# FenixCasePowerBoard.net
KiCad netlist of a schematic drawn in EAGLE
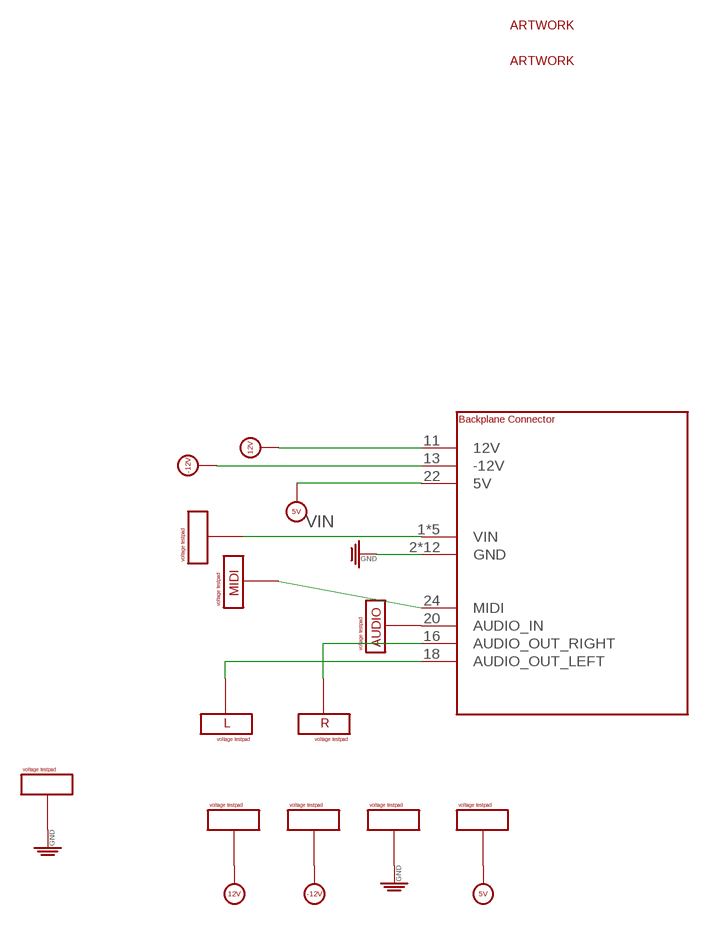
[diagram p0: schematic, sheet 1]
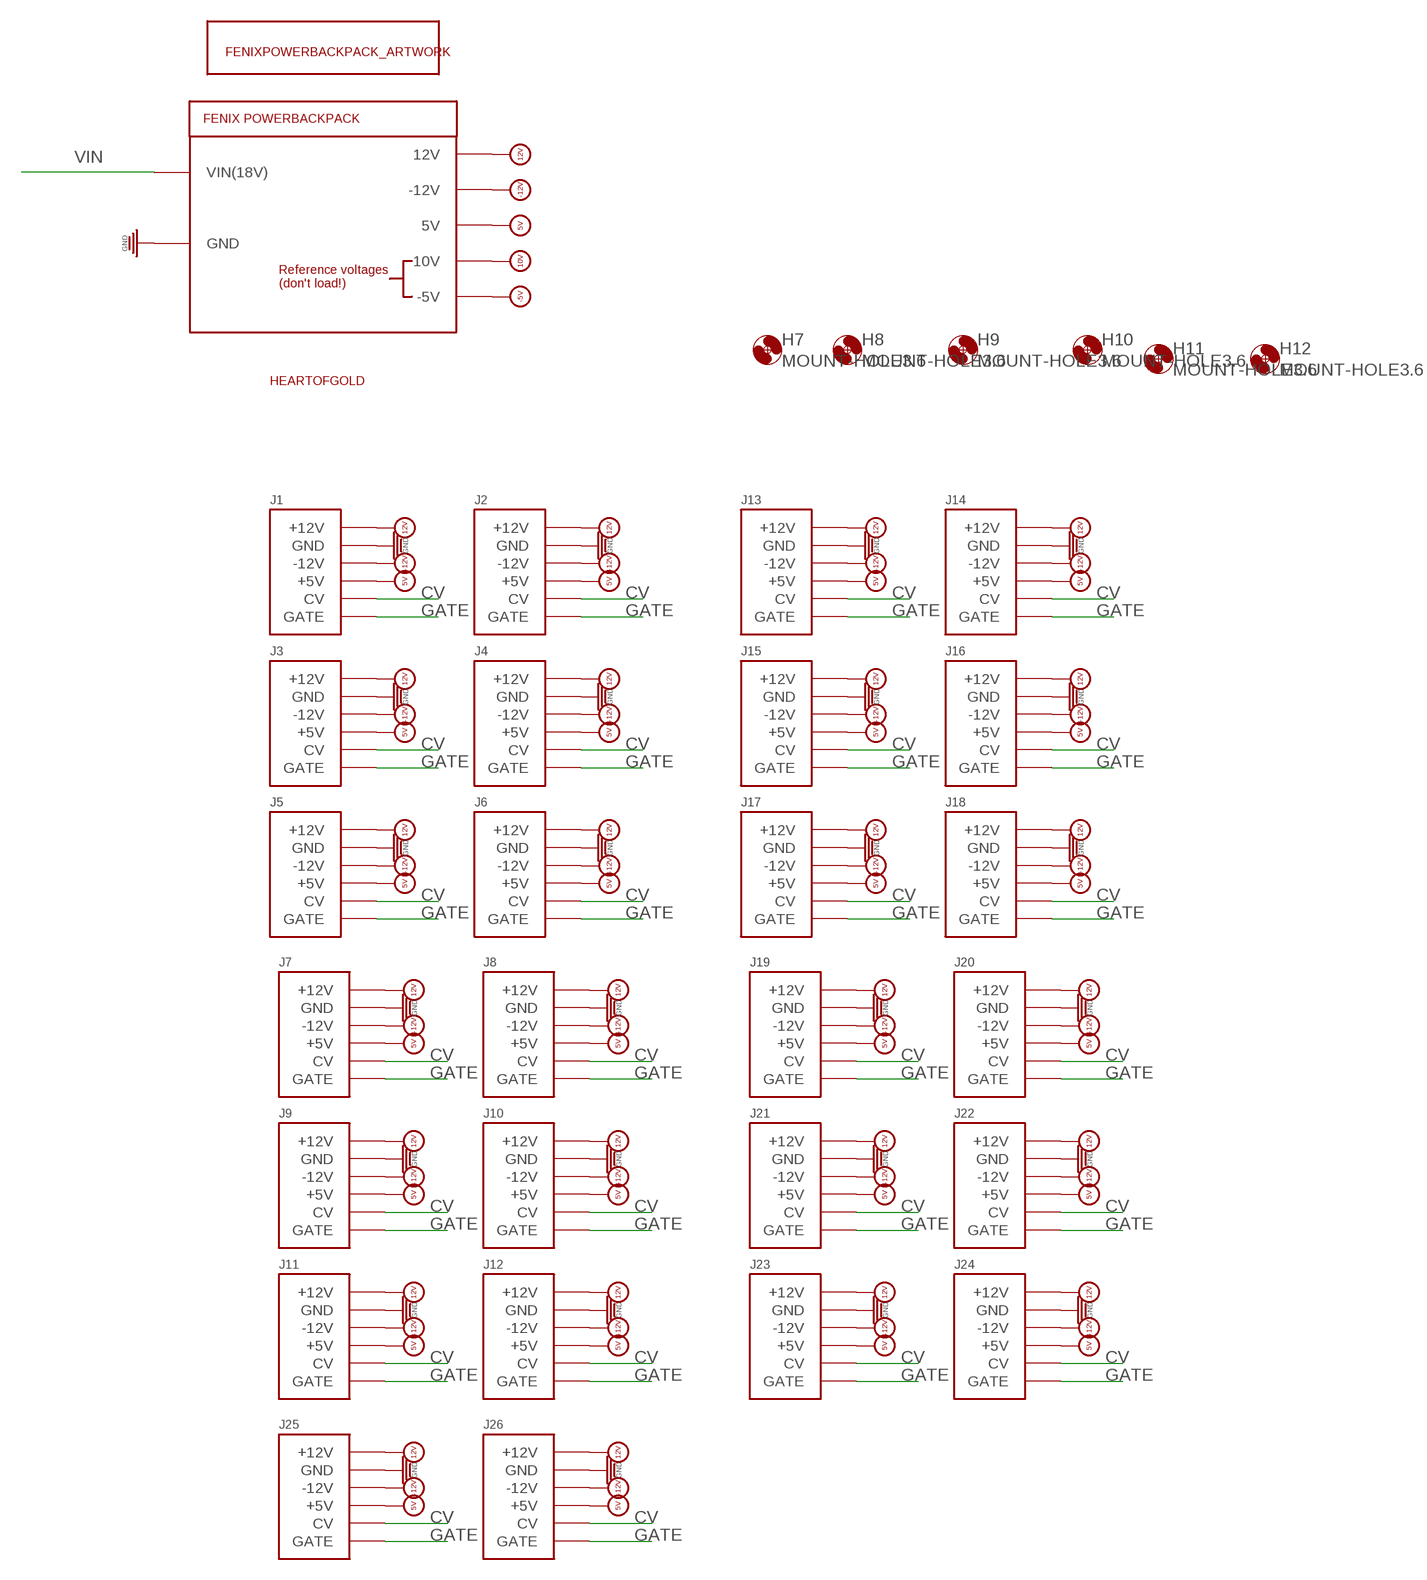
[diagram p1: schematic, sheet 3]

(export (version "E")
  (design (tool "Eeschema 10.0.6"))
  (components
    (comp (ref "H7")
      (value "MOUNT-HOLE3.6")
      (footprint "eagle-import:3,6")
      (libsource (lib "eagle-import") (part "MOUNT-HOLE3.6"))
    )
    (comp (ref "H8")
      (value "MOUNT-HOLE3.6")
      (footprint "eagle-import:3,6")
      (libsource (lib "eagle-import") (part "MOUNT-HOLE3.6"))
    )
    (comp (ref "H9")
      (value "MOUNT-HOLE3.6")
      (footprint "eagle-import:3,6")
      (libsource (lib "eagle-import") (part "MOUNT-HOLE3.6"))
    )
    (comp (ref "H10")
      (value "MOUNT-HOLE3.6")
      (footprint "eagle-import:3,6")
      (libsource (lib "eagle-import") (part "MOUNT-HOLE3.6"))
    )
    (comp (ref "H11")
      (value "MOUNT-HOLE3.6")
      (footprint "eagle-import:3,6")
      (libsource (lib "eagle-import") (part "MOUNT-HOLE3.6"))
    )
    (comp (ref "H12")
      (value "MOUNT-HOLE3.6")
      (footprint "eagle-import:3,6")
      (libsource (lib "eagle-import") (part "MOUNT-HOLE3.6"))
    )
    (comp (ref "J1")
      (value "POWERSHROUDED")
      (footprint "eagle-import:POWER_16_SHROUDED")
      (libsource (lib "eagle-import") (part "POWERSHROUDED"))
    )
    (comp (ref "J2")
      (value "POWERSHROUDED")
      (footprint "eagle-import:POWER_16_SHROUDED")
      (libsource (lib "eagle-import") (part "POWERSHROUDED"))
    )
    (comp (ref "J3")
      (value "POWERSHROUDED")
      (footprint "eagle-import:POWER_16_SHROUDED")
      (libsource (lib "eagle-import") (part "POWERSHROUDED"))
    )
    (comp (ref "J4")
      (value "POWERSHROUDED")
      (footprint "eagle-import:POWER_16_SHROUDED")
      (libsource (lib "eagle-import") (part "POWERSHROUDED"))
    )
    (comp (ref "J5")
      (value "POWERSHROUDED")
      (footprint "eagle-import:POWER_16_SHROUDED")
      (libsource (lib "eagle-import") (part "POWERSHROUDED"))
    )
    (comp (ref "J6")
      (value "POWERSHROUDED")
      (footprint "eagle-import:POWER_16_SHROUDED")
      (libsource (lib "eagle-import") (part "POWERSHROUDED"))
    )
    (comp (ref "J7")
      (value "POWERSHROUDED")
      (footprint "eagle-import:POWER_16_SHROUDED")
      (libsource (lib "eagle-import") (part "POWERSHROUDED"))
    )
    (comp (ref "J8")
      (value "POWERSHROUDED")
      (footprint "eagle-import:POWER_16_SHROUDED")
      (libsource (lib "eagle-import") (part "POWERSHROUDED"))
    )
    (comp (ref "J9")
      (value "POWERSHROUDED")
      (footprint "eagle-import:POWER_16_SHROUDED")
      (libsource (lib "eagle-import") (part "POWERSHROUDED"))
    )
    (comp (ref "J10")
      (value "POWERSHROUDED")
      (footprint "eagle-import:POWER_16_SHROUDED")
      (libsource (lib "eagle-import") (part "POWERSHROUDED"))
    )
    (comp (ref "J11")
      (value "POWERSHROUDED")
      (footprint "eagle-import:POWER_16_SHROUDED")
      (libsource (lib "eagle-import") (part "POWERSHROUDED"))
    )
    (comp (ref "J12")
      (value "POWERSHROUDED")
      (footprint "eagle-import:POWER_16_SHROUDED")
      (libsource (lib "eagle-import") (part "POWERSHROUDED"))
    )
    (comp (ref "J13")
      (value "POWERSHROUDED")
      (footprint "eagle-import:POWER_16_SHROUDED")
      (libsource (lib "eagle-import") (part "POWERSHROUDED"))
    )
    (comp (ref "J14")
      (value "POWERSHROUDED")
      (footprint "eagle-import:POWER_16_SHROUDED")
      (libsource (lib "eagle-import") (part "POWERSHROUDED"))
    )
    (comp (ref "J15")
      (value "POWERSHROUDED")
      (footprint "eagle-import:POWER_16_SHROUDED")
      (libsource (lib "eagle-import") (part "POWERSHROUDED"))
    )
    (comp (ref "J16")
      (value "POWERSHROUDED")
      (footprint "eagle-import:POWER_16_SHROUDED")
      (libsource (lib "eagle-import") (part "POWERSHROUDED"))
    )
    (comp (ref "J17")
      (value "POWERSHROUDED")
      (footprint "eagle-import:POWER_16_SHROUDED")
      (libsource (lib "eagle-import") (part "POWERSHROUDED"))
    )
    (comp (ref "J18")
      (value "POWERSHROUDED")
      (footprint "eagle-import:POWER_16_SHROUDED")
      (libsource (lib "eagle-import") (part "POWERSHROUDED"))
    )
    (comp (ref "J19")
      (value "POWERSHROUDED")
      (footprint "eagle-import:POWER_16_SHROUDED")
      (libsource (lib "eagle-import") (part "POWERSHROUDED"))
    )
    (comp (ref "J20")
      (value "POWERSHROUDED")
      (footprint "eagle-import:POWER_16_SHROUDED")
      (libsource (lib "eagle-import") (part "POWERSHROUDED"))
    )
    (comp (ref "J21")
      (value "POWERSHROUDED")
      (footprint "eagle-import:POWER_16_SHROUDED")
      (libsource (lib "eagle-import") (part "POWERSHROUDED"))
    )
    (comp (ref "J22")
      (value "POWERSHROUDED")
      (footprint "eagle-import:POWER_16_SHROUDED")
      (libsource (lib "eagle-import") (part "POWERSHROUDED"))
    )
    (comp (ref "J23")
      (value "POWERSHROUDED")
      (footprint "eagle-import:POWER_16_SHROUDED")
      (libsource (lib "eagle-import") (part "POWERSHROUDED"))
    )
    (comp (ref "J24")
      (value "POWERSHROUDED")
      (footprint "eagle-import:POWER_16_SHROUDED")
      (libsource (lib "eagle-import") (part "POWERSHROUDED"))
    )
    (comp (ref "J25")
      (value "POWERSHROUDED")
      (footprint "eagle-import:POWER_16_SHROUDED")
      (libsource (lib "eagle-import") (part "POWERSHROUDED"))
    )
    (comp (ref "J26")
      (value "POWERSHROUDED")
      (footprint "eagle-import:POWER_16_SHROUDED")
      (libsource (lib "eagle-import") (part "POWERSHROUDED"))
    )
    (comp (ref "U$5")
      (value "FENIXPOWERBACKPACKART_MODULE")
      (footprint "eagle-import:FENIXPOWERBACKPACK_MODULE")
      (libsource (lib "eagle-import") (part "FENIXPOWERBACKPACKART_MODULE"))
    )
    (comp (ref "U$10")
      (value "HEARTOFGOLD")
      (footprint "eagle-import:HEARTOFGOLD")
      (libsource (lib "eagle-import") (part "HEARTOFGOLD"))
    )
    (comp (ref "U$31")
      (value "FENIXPOWERBACKPACK_MODULE")
      (footprint "eagle-import:FENIXPOWERBACKPACK")
      (libsource (lib "eagle-import") (part "FENIXPOWERBACKPACK_MODULE"))
    )
    (comp (ref "U$1")
      (value "VOLTAGETESTPAD")
      (footprint "eagle-import:POWERTESTPAD")
      (fields (field (name "DESC") "MIDI"))
      (libsource (lib "eagle-import") (part "VOLTAGETESTPAD"))
    )
    (comp (ref "U$2")
      (value "VOLTAGETESTPAD")
      (footprint "eagle-import:POWERTESTPAD")
      (fields (field (name "DESC") "AUDIO"))
      (libsource (lib "eagle-import") (part "VOLTAGETESTPAD"))
    )
    (comp (ref "U$4")
      (value "VOLTAGETESTPAD_BIG")
      (footprint "eagle-import:POWERTESTPAD_BIG")
      (fields (field (name "DESC") "-12V"))
      (libsource (lib "eagle-import") (part "VOLTAGETESTPAD_BIG"))
    )
    (comp (ref "U$6")
      (value "VOLTAGETESTPAD_BIG")
      (footprint "eagle-import:POWERTESTPAD_BIG")
      (fields (field (name "DESC") "GND"))
      (libsource (lib "eagle-import") (part "VOLTAGETESTPAD_BIG"))
    )
    (comp (ref "U$7")
      (value "VOLTAGETESTPAD_BIG")
      (footprint "eagle-import:POWERTESTPAD_BIG")
      (fields (field (name "DESC") "5V"))
      (libsource (lib "eagle-import") (part "VOLTAGETESTPAD_BIG"))
    )
    (comp (ref "U$8")
      (value "BACKPLANECONNECTOR_VINPLANE")
      (footprint "eagle-import:BACKPLANECONNECTOR")
      (fields (field (name "DESC") "PowerSupplyInput"))
      (libsource (lib "eagle-import") (part "BACKPLANECONNECTOR_VINPLANE"))
    )
    (comp (ref "U$12")
      (value "VOLTAGETESTPAD_BIG")
      (footprint "eagle-import:POWERTESTPAD_BIG")
      (fields (field (name "DESC") "12V"))
      (libsource (lib "eagle-import") (part "VOLTAGETESTPAD_BIG"))
    )
    (comp (ref "U$20")
      (value "TINRS_ARTWORKTINYDATE")
      (footprint "eagle-import:JUSTATINYROCKET_DATECODE")
      (libsource (lib "eagle-import") (part "TINRS_ARTWORKTINYDATE"))
    )
    (comp (ref "U$21")
      (value "TINRS_ARTWORKTINYDATE")
      (footprint "eagle-import:JUSTATINYROCKET_DATECODE")
      (libsource (lib "eagle-import") (part "TINRS_ARTWORKTINYDATE"))
    )
    (comp (ref "U$29")
      (value "VOLTAGETESTPAD")
      (footprint "eagle-import:POWERTESTPAD")
      (fields (field (name "DESC") "L"))
      (libsource (lib "eagle-import") (part "VOLTAGETESTPAD"))
    )
    (comp (ref "U$30")
      (value "VOLTAGETESTPAD")
      (footprint "eagle-import:POWERTESTPAD")
      (fields (field (name "DESC") "R"))
      (libsource (lib "eagle-import") (part "VOLTAGETESTPAD"))
    )
    (comp (ref "U$104")
      (value "VOLTAGETESTPAD_BIG")
      (footprint "eagle-import:POWERTESTPAD_BIG")
      (fields (field (name "DESC") "VIN"))
      (libsource (lib "eagle-import") (part "VOLTAGETESTPAD_BIG"))
    )
    (comp (ref "U$105")
      (value "VOLTAGETESTPAD_BIG")
      (footprint "eagle-import:POWERTESTPAD_BIG")
      (fields (field (name "DESC") "GND"))
      (libsource (lib "eagle-import") (part "VOLTAGETESTPAD_BIG"))
    )
  )
  (nets
    (net (code "1") (name "-5V") (class "Default")
      (node (ref "U$31") (pin "-5V") (pinfunction "-5V_-5V") (pintype "bidirectional"))
      (node (ref "U$31") (pin "-5V@2") (pinfunction "-5V_-5V@2") (pintype "bidirectional"))
    )
    (net (code "2") (name "-12V") (class "Default")
      (node (ref "J1") (pin "1") (pinfunction "-12V_1") (pintype "bidirectional"))
      (node (ref "J1") (pin "2") (pinfunction "-12V_2") (pintype "bidirectional"))
      (node (ref "J10") (pin "1") (pinfunction "-12V_1") (pintype "bidirectional"))
      (node (ref "J10") (pin "2") (pinfunction "-12V_2") (pintype "bidirectional"))
      (node (ref "J11") (pin "1") (pinfunction "-12V_1") (pintype "bidirectional"))
      (node (ref "J11") (pin "2") (pinfunction "-12V_2") (pintype "bidirectional"))
      (node (ref "J12") (pin "1") (pinfunction "-12V_1") (pintype "bidirectional"))
      (node (ref "J12") (pin "2") (pinfunction "-12V_2") (pintype "bidirectional"))
      (node (ref "J13") (pin "1") (pinfunction "-12V_1") (pintype "bidirectional"))
      (node (ref "J13") (pin "2") (pinfunction "-12V_2") (pintype "bidirectional"))
      (node (ref "J14") (pin "1") (pinfunction "-12V_1") (pintype "bidirectional"))
      (node (ref "J14") (pin "2") (pinfunction "-12V_2") (pintype "bidirectional"))
      (node (ref "J15") (pin "1") (pinfunction "-12V_1") (pintype "bidirectional"))
      (node (ref "J15") (pin "2") (pinfunction "-12V_2") (pintype "bidirectional"))
      (node (ref "J16") (pin "1") (pinfunction "-12V_1") (pintype "bidirectional"))
      (node (ref "J16") (pin "2") (pinfunction "-12V_2") (pintype "bidirectional"))
      (node (ref "J17") (pin "1") (pinfunction "-12V_1") (pintype "bidirectional"))
      (node (ref "J17") (pin "2") (pinfunction "-12V_2") (pintype "bidirectional"))
      (node (ref "J18") (pin "1") (pinfunction "-12V_1") (pintype "bidirectional"))
      (node (ref "J18") (pin "2") (pinfunction "-12V_2") (pintype "bidirectional"))
      (node (ref "J19") (pin "1") (pinfunction "-12V_1") (pintype "bidirectional"))
      (node (ref "J19") (pin "2") (pinfunction "-12V_2") (pintype "bidirectional"))
      (node (ref "J2") (pin "1") (pinfunction "-12V_1") (pintype "bidirectional"))
      (node (ref "J2") (pin "2") (pinfunction "-12V_2") (pintype "bidirectional"))
      (node (ref "J20") (pin "1") (pinfunction "-12V_1") (pintype "bidirectional"))
      (node (ref "J20") (pin "2") (pinfunction "-12V_2") (pintype "bidirectional"))
      (node (ref "J21") (pin "1") (pinfunction "-12V_1") (pintype "bidirectional"))
      (node (ref "J21") (pin "2") (pinfunction "-12V_2") (pintype "bidirectional"))
      (node (ref "J22") (pin "1") (pinfunction "-12V_1") (pintype "bidirectional"))
      (node (ref "J22") (pin "2") (pinfunction "-12V_2") (pintype "bidirectional"))
      (node (ref "J23") (pin "1") (pinfunction "-12V_1") (pintype "bidirectional"))
      (node (ref "J23") (pin "2") (pinfunction "-12V_2") (pintype "bidirectional"))
      (node (ref "J24") (pin "1") (pinfunction "-12V_1") (pintype "bidirectional"))
      (node (ref "J24") (pin "2") (pinfunction "-12V_2") (pintype "bidirectional"))
      (node (ref "J25") (pin "1") (pinfunction "-12V_1") (pintype "bidirectional"))
      (node (ref "J25") (pin "2") (pinfunction "-12V_2") (pintype "bidirectional"))
      (node (ref "J26") (pin "1") (pinfunction "-12V_1") (pintype "bidirectional"))
      (node (ref "J26") (pin "2") (pinfunction "-12V_2") (pintype "bidirectional"))
      (node (ref "J3") (pin "1") (pinfunction "-12V_1") (pintype "bidirectional"))
      (node (ref "J3") (pin "2") (pinfunction "-12V_2") (pintype "bidirectional"))
      (node (ref "J4") (pin "1") (pinfunction "-12V_1") (pintype "bidirectional"))
      (node (ref "J4") (pin "2") (pinfunction "-12V_2") (pintype "bidirectional"))
      (node (ref "J5") (pin "1") (pinfunction "-12V_1") (pintype "bidirectional"))
      (node (ref "J5") (pin "2") (pinfunction "-12V_2") (pintype "bidirectional"))
      (node (ref "J6") (pin "1") (pinfunction "-12V_1") (pintype "bidirectional"))
      (node (ref "J6") (pin "2") (pinfunction "-12V_2") (pintype "bidirectional"))
      (node (ref "J7") (pin "1") (pinfunction "-12V_1") (pintype "bidirectional"))
      (node (ref "J7") (pin "2") (pinfunction "-12V_2") (pintype "bidirectional"))
      (node (ref "J8") (pin "1") (pinfunction "-12V_1") (pintype "bidirectional"))
      (node (ref "J8") (pin "2") (pinfunction "-12V_2") (pintype "bidirectional"))
      (node (ref "J9") (pin "1") (pinfunction "-12V_1") (pintype "bidirectional"))
      (node (ref "J9") (pin "2") (pinfunction "-12V_2") (pintype "bidirectional"))
      (node (ref "U$31") (pin "-12V@1") (pinfunction "-12V_-12V@1") (pintype "bidirectional"))
      (node (ref "U$31") (pin "-12V@2") (pinfunction "-12V_-12V@2") (pintype "bidirectional"))
      (node (ref "U$31") (pin "-12V@3") (pinfunction "-12V_-12V@3") (pintype "bidirectional"))
      (node (ref "U$4") (pin "P$1") (pinfunction "VOLTAGE_P$1") (pintype "bidirectional"))
      (node (ref "U$4") (pin "P$2") (pinfunction "VOLTAGE_P$2") (pintype "bidirectional"))
      (node (ref "U$4") (pin "P$3") (pinfunction "VOLTAGE_P$3") (pintype "bidirectional"))
      (node (ref "U$8") (pin "13") (pinfunction "-12V_13") (pintype "bidirectional"))
    )
    (net (code "3") (name "5V") (class "Default")
      (node (ref "J1") (pin "11") (pinfunction "+5V_11") (pintype "bidirectional"))
      (node (ref "J1") (pin "12") (pinfunction "+5V_12") (pintype "bidirectional"))
      (node (ref "J10") (pin "11") (pinfunction "+5V_11") (pintype "bidirectional"))
      (node (ref "J10") (pin "12") (pinfunction "+5V_12") (pintype "bidirectional"))
      (node (ref "J11") (pin "11") (pinfunction "+5V_11") (pintype "bidirectional"))
      (node (ref "J11") (pin "12") (pinfunction "+5V_12") (pintype "bidirectional"))
      (node (ref "J12") (pin "11") (pinfunction "+5V_11") (pintype "bidirectional"))
      (node (ref "J12") (pin "12") (pinfunction "+5V_12") (pintype "bidirectional"))
      (node (ref "J13") (pin "11") (pinfunction "+5V_11") (pintype "bidirectional"))
      (node (ref "J13") (pin "12") (pinfunction "+5V_12") (pintype "bidirectional"))
      (node (ref "J14") (pin "11") (pinfunction "+5V_11") (pintype "bidirectional"))
      (node (ref "J14") (pin "12") (pinfunction "+5V_12") (pintype "bidirectional"))
      (node (ref "J15") (pin "11") (pinfunction "+5V_11") (pintype "bidirectional"))
      (node (ref "J15") (pin "12") (pinfunction "+5V_12") (pintype "bidirectional"))
      (node (ref "J16") (pin "11") (pinfunction "+5V_11") (pintype "bidirectional"))
      (node (ref "J16") (pin "12") (pinfunction "+5V_12") (pintype "bidirectional"))
      (node (ref "J17") (pin "11") (pinfunction "+5V_11") (pintype "bidirectional"))
      (node (ref "J17") (pin "12") (pinfunction "+5V_12") (pintype "bidirectional"))
      (node (ref "J18") (pin "11") (pinfunction "+5V_11") (pintype "bidirectional"))
      (node (ref "J18") (pin "12") (pinfunction "+5V_12") (pintype "bidirectional"))
      (node (ref "J19") (pin "11") (pinfunction "+5V_11") (pintype "bidirectional"))
      (node (ref "J19") (pin "12") (pinfunction "+5V_12") (pintype "bidirectional"))
      (node (ref "J2") (pin "11") (pinfunction "+5V_11") (pintype "bidirectional"))
      (node (ref "J2") (pin "12") (pinfunction "+5V_12") (pintype "bidirectional"))
      (node (ref "J20") (pin "11") (pinfunction "+5V_11") (pintype "bidirectional"))
      (node (ref "J20") (pin "12") (pinfunction "+5V_12") (pintype "bidirectional"))
      (node (ref "J21") (pin "11") (pinfunction "+5V_11") (pintype "bidirectional"))
      (node (ref "J21") (pin "12") (pinfunction "+5V_12") (pintype "bidirectional"))
      (node (ref "J22") (pin "11") (pinfunction "+5V_11") (pintype "bidirectional"))
      (node (ref "J22") (pin "12") (pinfunction "+5V_12") (pintype "bidirectional"))
      (node (ref "J23") (pin "11") (pinfunction "+5V_11") (pintype "bidirectional"))
      (node (ref "J23") (pin "12") (pinfunction "+5V_12") (pintype "bidirectional"))
      (node (ref "J24") (pin "11") (pinfunction "+5V_11") (pintype "bidirectional"))
      (node (ref "J24") (pin "12") (pinfunction "+5V_12") (pintype "bidirectional"))
      (node (ref "J25") (pin "11") (pinfunction "+5V_11") (pintype "bidirectional"))
      (node (ref "J25") (pin "12") (pinfunction "+5V_12") (pintype "bidirectional"))
      (node (ref "J26") (pin "11") (pinfunction "+5V_11") (pintype "bidirectional"))
      (node (ref "J26") (pin "12") (pinfunction "+5V_12") (pintype "bidirectional"))
      (node (ref "J3") (pin "11") (pinfunction "+5V_11") (pintype "bidirectional"))
      (node (ref "J3") (pin "12") (pinfunction "+5V_12") (pintype "bidirectional"))
      (node (ref "J4") (pin "11") (pinfunction "+5V_11") (pintype "bidirectional"))
      (node (ref "J4") (pin "12") (pinfunction "+5V_12") (pintype "bidirectional"))
      (node (ref "J5") (pin "11") (pinfunction "+5V_11") (pintype "bidirectional"))
      (node (ref "J5") (pin "12") (pinfunction "+5V_12") (pintype "bidirectional"))
      (node (ref "J6") (pin "11") (pinfunction "+5V_11") (pintype "bidirectional"))
      (node (ref "J6") (pin "12") (pinfunction "+5V_12") (pintype "bidirectional"))
      (node (ref "J7") (pin "11") (pinfunction "+5V_11") (pintype "bidirectional"))
      (node (ref "J7") (pin "12") (pinfunction "+5V_12") (pintype "bidirectional"))
      (node (ref "J8") (pin "11") (pinfunction "+5V_11") (pintype "bidirectional"))
      (node (ref "J8") (pin "12") (pinfunction "+5V_12") (pintype "bidirectional"))
      (node (ref "J9") (pin "11") (pinfunction "+5V_11") (pintype "bidirectional"))
      (node (ref "J9") (pin "12") (pinfunction "+5V_12") (pintype "bidirectional"))
      (node (ref "U$31") (pin "5V@1") (pinfunction "5V_5V@1") (pintype "bidirectional"))
      (node (ref "U$31") (pin "5V@2") (pinfunction "5V_5V@2") (pintype "bidirectional"))
      (node (ref "U$31") (pin "5V@3") (pinfunction "5V_5V@3") (pintype "bidirectional"))
      (node (ref "U$31") (pin "5V@4") (pinfunction "5V_5V@4") (pintype "bidirectional"))
      (node (ref "U$7") (pin "P$1") (pinfunction "VOLTAGE_P$1") (pintype "bidirectional"))
      (node (ref "U$7") (pin "P$2") (pinfunction "VOLTAGE_P$2") (pintype "bidirectional"))
      (node (ref "U$7") (pin "P$3") (pinfunction "VOLTAGE_P$3") (pintype "bidirectional"))
      (node (ref "U$8") (pin "22") (pinfunction "5V_22") (pintype "bidirectional"))
    )
    (net (code "4") (name "10V") (class "Default")
      (node (ref "U$31") (pin "10V") (pinfunction "10V_10V") (pintype "bidirectional"))
      (node (ref "U$31") (pin "10V@2") (pinfunction "10V_10V@2") (pintype "bidirectional"))
    )
    (net (code "5") (name "12V") (class "Default")
      (node (ref "J1") (pin "10") (pinfunction "+12V_10") (pintype "bidirectional"))
      (node (ref "J1") (pin "9") (pinfunction "+12V_9") (pintype "bidirectional"))
      (node (ref "J10") (pin "10") (pinfunction "+12V_10") (pintype "bidirectional"))
      (node (ref "J10") (pin "9") (pinfunction "+12V_9") (pintype "bidirectional"))
      (node (ref "J11") (pin "10") (pinfunction "+12V_10") (pintype "bidirectional"))
      (node (ref "J11") (pin "9") (pinfunction "+12V_9") (pintype "bidirectional"))
      (node (ref "J12") (pin "10") (pinfunction "+12V_10") (pintype "bidirectional"))
      (node (ref "J12") (pin "9") (pinfunction "+12V_9") (pintype "bidirectional"))
      (node (ref "J13") (pin "10") (pinfunction "+12V_10") (pintype "bidirectional"))
      (node (ref "J13") (pin "9") (pinfunction "+12V_9") (pintype "bidirectional"))
      (node (ref "J14") (pin "10") (pinfunction "+12V_10") (pintype "bidirectional"))
      (node (ref "J14") (pin "9") (pinfunction "+12V_9") (pintype "bidirectional"))
      (node (ref "J15") (pin "10") (pinfunction "+12V_10") (pintype "bidirectional"))
      (node (ref "J15") (pin "9") (pinfunction "+12V_9") (pintype "bidirectional"))
      (node (ref "J16") (pin "10") (pinfunction "+12V_10") (pintype "bidirectional"))
      (node (ref "J16") (pin "9") (pinfunction "+12V_9") (pintype "bidirectional"))
      (node (ref "J17") (pin "10") (pinfunction "+12V_10") (pintype "bidirectional"))
      (node (ref "J17") (pin "9") (pinfunction "+12V_9") (pintype "bidirectional"))
      (node (ref "J18") (pin "10") (pinfunction "+12V_10") (pintype "bidirectional"))
      (node (ref "J18") (pin "9") (pinfunction "+12V_9") (pintype "bidirectional"))
      (node (ref "J19") (pin "10") (pinfunction "+12V_10") (pintype "bidirectional"))
      (node (ref "J19") (pin "9") (pinfunction "+12V_9") (pintype "bidirectional"))
      (node (ref "J2") (pin "10") (pinfunction "+12V_10") (pintype "bidirectional"))
      (node (ref "J2") (pin "9") (pinfunction "+12V_9") (pintype "bidirectional"))
      (node (ref "J20") (pin "10") (pinfunction "+12V_10") (pintype "bidirectional"))
      (node (ref "J20") (pin "9") (pinfunction "+12V_9") (pintype "bidirectional"))
      (node (ref "J21") (pin "10") (pinfunction "+12V_10") (pintype "bidirectional"))
      (node (ref "J21") (pin "9") (pinfunction "+12V_9") (pintype "bidirectional"))
      (node (ref "J22") (pin "10") (pinfunction "+12V_10") (pintype "bidirectional"))
      (node (ref "J22") (pin "9") (pinfunction "+12V_9") (pintype "bidirectional"))
      (node (ref "J23") (pin "10") (pinfunction "+12V_10") (pintype "bidirectional"))
      (node (ref "J23") (pin "9") (pinfunction "+12V_9") (pintype "bidirectional"))
      (node (ref "J24") (pin "10") (pinfunction "+12V_10") (pintype "bidirectional"))
      (node (ref "J24") (pin "9") (pinfunction "+12V_9") (pintype "bidirectional"))
      (node (ref "J25") (pin "10") (pinfunction "+12V_10") (pintype "bidirectional"))
      (node (ref "J25") (pin "9") (pinfunction "+12V_9") (pintype "bidirectional"))
      (node (ref "J26") (pin "10") (pinfunction "+12V_10") (pintype "bidirectional"))
      (node (ref "J26") (pin "9") (pinfunction "+12V_9") (pintype "bidirectional"))
      (node (ref "J3") (pin "10") (pinfunction "+12V_10") (pintype "bidirectional"))
      (node (ref "J3") (pin "9") (pinfunction "+12V_9") (pintype "bidirectional"))
      (node (ref "J4") (pin "10") (pinfunction "+12V_10") (pintype "bidirectional"))
      (node (ref "J4") (pin "9") (pinfunction "+12V_9") (pintype "bidirectional"))
      (node (ref "J5") (pin "10") (pinfunction "+12V_10") (pintype "bidirectional"))
      (node (ref "J5") (pin "9") (pinfunction "+12V_9") (pintype "bidirectional"))
      (node (ref "J6") (pin "10") (pinfunction "+12V_10") (pintype "bidirectional"))
      (node (ref "J6") (pin "9") (pinfunction "+12V_9") (pintype "bidirectional"))
      (node (ref "J7") (pin "10") (pinfunction "+12V_10") (pintype "bidirectional"))
      (node (ref "J7") (pin "9") (pinfunction "+12V_9") (pintype "bidirectional"))
      (node (ref "J8") (pin "10") (pinfunction "+12V_10") (pintype "bidirectional"))
      (node (ref "J8") (pin "9") (pinfunction "+12V_9") (pintype "bidirectional"))
      (node (ref "J9") (pin "10") (pinfunction "+12V_10") (pintype "bidirectional"))
      (node (ref "J9") (pin "9") (pinfunction "+12V_9") (pintype "bidirectional"))
      (node (ref "U$12") (pin "P$1") (pinfunction "VOLTAGE_P$1") (pintype "bidirectional"))
      (node (ref "U$12") (pin "P$2") (pinfunction "VOLTAGE_P$2") (pintype "bidirectional"))
      (node (ref "U$12") (pin "P$3") (pinfunction "VOLTAGE_P$3") (pintype "bidirectional"))
      (node (ref "U$31") (pin "12V@1") (pinfunction "12V_12V@1") (pintype "bidirectional"))
      (node (ref "U$31") (pin "12V@2") (pinfunction "12V_12V@2") (pintype "bidirectional"))
      (node (ref "U$31") (pin "12V@4") (pinfunction "12V_12V@4") (pintype "bidirectional"))
      (node (ref "U$8") (pin "11") (pinfunction "12V_11") (pintype "bidirectional"))
    )
    (net (code "6") (name "CV") (class "Default")
      (node (ref "J1") (pin "13") (pinfunction "CV_13") (pintype "bidirectional"))
      (node (ref "J1") (pin "14") (pinfunction "CV_14") (pintype "bidirectional"))
      (node (ref "J10") (pin "13") (pinfunction "CV_13") (pintype "bidirectional"))
      (node (ref "J10") (pin "14") (pinfunction "CV_14") (pintype "bidirectional"))
      (node (ref "J11") (pin "13") (pinfunction "CV_13") (pintype "bidirectional"))
      (node (ref "J11") (pin "14") (pinfunction "CV_14") (pintype "bidirectional"))
      (node (ref "J12") (pin "13") (pinfunction "CV_13") (pintype "bidirectional"))
      (node (ref "J12") (pin "14") (pinfunction "CV_14") (pintype "bidirectional"))
      (node (ref "J13") (pin "13") (pinfunction "CV_13") (pintype "bidirectional"))
      (node (ref "J13") (pin "14") (pinfunction "CV_14") (pintype "bidirectional"))
      (node (ref "J14") (pin "13") (pinfunction "CV_13") (pintype "bidirectional"))
      (node (ref "J14") (pin "14") (pinfunction "CV_14") (pintype "bidirectional"))
      (node (ref "J15") (pin "13") (pinfunction "CV_13") (pintype "bidirectional"))
      (node (ref "J15") (pin "14") (pinfunction "CV_14") (pintype "bidirectional"))
      (node (ref "J16") (pin "13") (pinfunction "CV_13") (pintype "bidirectional"))
      (node (ref "J16") (pin "14") (pinfunction "CV_14") (pintype "bidirectional"))
      (node (ref "J17") (pin "13") (pinfunction "CV_13") (pintype "bidirectional"))
      (node (ref "J17") (pin "14") (pinfunction "CV_14") (pintype "bidirectional"))
      (node (ref "J18") (pin "13") (pinfunction "CV_13") (pintype "bidirectional"))
      (node (ref "J18") (pin "14") (pinfunction "CV_14") (pintype "bidirectional"))
      (node (ref "J19") (pin "13") (pinfunction "CV_13") (pintype "bidirectional"))
      (node (ref "J19") (pin "14") (pinfunction "CV_14") (pintype "bidirectional"))
      (node (ref "J2") (pin "13") (pinfunction "CV_13") (pintype "bidirectional"))
      (node (ref "J2") (pin "14") (pinfunction "CV_14") (pintype "bidirectional"))
      (node (ref "J20") (pin "13") (pinfunction "CV_13") (pintype "bidirectional"))
      (node (ref "J20") (pin "14") (pinfunction "CV_14") (pintype "bidirectional"))
      (node (ref "J21") (pin "13") (pinfunction "CV_13") (pintype "bidirectional"))
      (node (ref "J21") (pin "14") (pinfunction "CV_14") (pintype "bidirectional"))
      (node (ref "J22") (pin "13") (pinfunction "CV_13") (pintype "bidirectional"))
      (node (ref "J22") (pin "14") (pinfunction "CV_14") (pintype "bidirectional"))
      (node (ref "J23") (pin "13") (pinfunction "CV_13") (pintype "bidirectional"))
      (node (ref "J23") (pin "14") (pinfunction "CV_14") (pintype "bidirectional"))
      (node (ref "J24") (pin "13") (pinfunction "CV_13") (pintype "bidirectional"))
      (node (ref "J24") (pin "14") (pinfunction "CV_14") (pintype "bidirectional"))
      (node (ref "J25") (pin "13") (pinfunction "CV_13") (pintype "bidirectional"))
      (node (ref "J25") (pin "14") (pinfunction "CV_14") (pintype "bidirectional"))
      (node (ref "J26") (pin "13") (pinfunction "CV_13") (pintype "bidirectional"))
      (node (ref "J26") (pin "14") (pinfunction "CV_14") (pintype "bidirectional"))
      (node (ref "J3") (pin "13") (pinfunction "CV_13") (pintype "bidirectional"))
      (node (ref "J3") (pin "14") (pinfunction "CV_14") (pintype "bidirectional"))
      (node (ref "J4") (pin "13") (pinfunction "CV_13") (pintype "bidirectional"))
      (node (ref "J4") (pin "14") (pinfunction "CV_14") (pintype "bidirectional"))
      (node (ref "J5") (pin "13") (pinfunction "CV_13") (pintype "bidirectional"))
      (node (ref "J5") (pin "14") (pinfunction "CV_14") (pintype "bidirectional"))
      (node (ref "J6") (pin "13") (pinfunction "CV_13") (pintype "bidirectional"))
      (node (ref "J6") (pin "14") (pinfunction "CV_14") (pintype "bidirectional"))
      (node (ref "J7") (pin "13") (pinfunction "CV_13") (pintype "bidirectional"))
      (node (ref "J7") (pin "14") (pinfunction "CV_14") (pintype "bidirectional"))
      (node (ref "J8") (pin "13") (pinfunction "CV_13") (pintype "bidirectional"))
      (node (ref "J8") (pin "14") (pinfunction "CV_14") (pintype "bidirectional"))
      (node (ref "J9") (pin "13") (pinfunction "CV_13") (pintype "bidirectional"))
      (node (ref "J9") (pin "14") (pinfunction "CV_14") (pintype "bidirectional"))
    )
    (net (code "7") (name "GATE") (class "Default")
      (node (ref "J1") (pin "15") (pinfunction "GATE_15") (pintype "bidirectional"))
      (node (ref "J1") (pin "16") (pinfunction "GATE_16") (pintype "bidirectional"))
      (node (ref "J10") (pin "15") (pinfunction "GATE_15") (pintype "bidirectional"))
      (node (ref "J10") (pin "16") (pinfunction "GATE_16") (pintype "bidirectional"))
      (node (ref "J11") (pin "15") (pinfunction "GATE_15") (pintype "bidirectional"))
      (node (ref "J11") (pin "16") (pinfunction "GATE_16") (pintype "bidirectional"))
      (node (ref "J12") (pin "15") (pinfunction "GATE_15") (pintype "bidirectional"))
      (node (ref "J12") (pin "16") (pinfunction "GATE_16") (pintype "bidirectional"))
      (node (ref "J13") (pin "15") (pinfunction "GATE_15") (pintype "bidirectional"))
      (node (ref "J13") (pin "16") (pinfunction "GATE_16") (pintype "bidirectional"))
      (node (ref "J14") (pin "15") (pinfunction "GATE_15") (pintype "bidirectional"))
      (node (ref "J14") (pin "16") (pinfunction "GATE_16") (pintype "bidirectional"))
      (node (ref "J15") (pin "15") (pinfunction "GATE_15") (pintype "bidirectional"))
      (node (ref "J15") (pin "16") (pinfunction "GATE_16") (pintype "bidirectional"))
      (node (ref "J16") (pin "15") (pinfunction "GATE_15") (pintype "bidirectional"))
      (node (ref "J16") (pin "16") (pinfunction "GATE_16") (pintype "bidirectional"))
      (node (ref "J17") (pin "15") (pinfunction "GATE_15") (pintype "bidirectional"))
      (node (ref "J17") (pin "16") (pinfunction "GATE_16") (pintype "bidirectional"))
      (node (ref "J18") (pin "15") (pinfunction "GATE_15") (pintype "bidirectional"))
      (node (ref "J18") (pin "16") (pinfunction "GATE_16") (pintype "bidirectional"))
      (node (ref "J19") (pin "15") (pinfunction "GATE_15") (pintype "bidirectional"))
      (node (ref "J19") (pin "16") (pinfunction "GATE_16") (pintype "bidirectional"))
      (node (ref "J2") (pin "15") (pinfunction "GATE_15") (pintype "bidirectional"))
      (node (ref "J2") (pin "16") (pinfunction "GATE_16") (pintype "bidirectional"))
      (node (ref "J20") (pin "15") (pinfunction "GATE_15") (pintype "bidirectional"))
      (node (ref "J20") (pin "16") (pinfunction "GATE_16") (pintype "bidirectional"))
      (node (ref "J21") (pin "15") (pinfunction "GATE_15") (pintype "bidirectional"))
      (node (ref "J21") (pin "16") (pinfunction "GATE_16") (pintype "bidirectional"))
      (node (ref "J22") (pin "15") (pinfunction "GATE_15") (pintype "bidirectional"))
      (node (ref "J22") (pin "16") (pinfunction "GATE_16") (pintype "bidirectional"))
      (node (ref "J23") (pin "15") (pinfunction "GATE_15") (pintype "bidirectional"))
      (node (ref "J23") (pin "16") (pinfunction "GATE_16") (pintype "bidirectional"))
      (node (ref "J24") (pin "15") (pinfunction "GATE_15") (pintype "bidirectional"))
      (node (ref "J24") (pin "16") (pinfunction "GATE_16") (pintype "bidirectional"))
      (node (ref "J25") (pin "15") (pinfunction "GATE_15") (pintype "bidirectional"))
      (node (ref "J25") (pin "16") (pinfunction "GATE_16") (pintype "bidirectional"))
      (node (ref "J26") (pin "15") (pinfunction "GATE_15") (pintype "bidirectional"))
      (node (ref "J26") (pin "16") (pinfunction "GATE_16") (pintype "bidirectional"))
      (node (ref "J3") (pin "15") (pinfunction "GATE_15") (pintype "bidirectional"))
      (node (ref "J3") (pin "16") (pinfunction "GATE_16") (pintype "bidirectional"))
      (node (ref "J4") (pin "15") (pinfunction "GATE_15") (pintype "bidirectional"))
      (node (ref "J4") (pin "16") (pinfunction "GATE_16") (pintype "bidirectional"))
      (node (ref "J5") (pin "15") (pinfunction "GATE_15") (pintype "bidirectional"))
      (node (ref "J5") (pin "16") (pinfunction "GATE_16") (pintype "bidirectional"))
      (node (ref "J6") (pin "15") (pinfunction "GATE_15") (pintype "bidirectional"))
      (node (ref "J6") (pin "16") (pinfunction "GATE_16") (pintype "bidirectional"))
      (node (ref "J7") (pin "15") (pinfunction "GATE_15") (pintype "bidirectional"))
      (node (ref "J7") (pin "16") (pinfunction "GATE_16") (pintype "bidirectional"))
      (node (ref "J8") (pin "15") (pinfunction "GATE_15") (pintype "bidirectional"))
      (node (ref "J8") (pin "16") (pinfunction "GATE_16") (pintype "bidirectional"))
      (node (ref "J9") (pin "15") (pinfunction "GATE_15") (pintype "bidirectional"))
      (node (ref "J9") (pin "16") (pinfunction "GATE_16") (pintype "bidirectional"))
    )
    (net (code "8") (name "GND") (class "Default")
      (node (ref "J1") (pin "3") (pinfunction "GND_3") (pintype "bidirectional"))
      (node (ref "J1") (pin "4") (pinfunction "GND_4") (pintype "bidirectional"))
      (node (ref "J1") (pin "5") (pinfunction "GND_5") (pintype "bidirectional"))
      (node (ref "J1") (pin "6") (pinfunction "GND_6") (pintype "bidirectional"))
      (node (ref "J1") (pin "7") (pinfunction "GND_7") (pintype "bidirectional"))
      (node (ref "J1") (pin "8") (pinfunction "GND_8") (pintype "bidirectional"))
      (node (ref "J10") (pin "3") (pinfunction "GND_3") (pintype "bidirectional"))
      (node (ref "J10") (pin "4") (pinfunction "GND_4") (pintype "bidirectional"))
      (node (ref "J10") (pin "5") (pinfunction "GND_5") (pintype "bidirectional"))
      (node (ref "J10") (pin "6") (pinfunction "GND_6") (pintype "bidirectional"))
      (node (ref "J10") (pin "7") (pinfunction "GND_7") (pintype "bidirectional"))
      (node (ref "J10") (pin "8") (pinfunction "GND_8") (pintype "bidirectional"))
      (node (ref "J11") (pin "3") (pinfunction "GND_3") (pintype "bidirectional"))
      (node (ref "J11") (pin "4") (pinfunction "GND_4") (pintype "bidirectional"))
      (node (ref "J11") (pin "5") (pinfunction "GND_5") (pintype "bidirectional"))
      (node (ref "J11") (pin "6") (pinfunction "GND_6") (pintype "bidirectional"))
      (node (ref "J11") (pin "7") (pinfunction "GND_7") (pintype "bidirectional"))
      (node (ref "J11") (pin "8") (pinfunction "GND_8") (pintype "bidirectional"))
      (node (ref "J12") (pin "3") (pinfunction "GND_3") (pintype "bidirectional"))
      (node (ref "J12") (pin "4") (pinfunction "GND_4") (pintype "bidirectional"))
      (node (ref "J12") (pin "5") (pinfunction "GND_5") (pintype "bidirectional"))
      (node (ref "J12") (pin "6") (pinfunction "GND_6") (pintype "bidirectional"))
      (node (ref "J12") (pin "7") (pinfunction "GND_7") (pintype "bidirectional"))
      (node (ref "J12") (pin "8") (pinfunction "GND_8") (pintype "bidirectional"))
      (node (ref "J13") (pin "3") (pinfunction "GND_3") (pintype "bidirectional"))
      (node (ref "J13") (pin "4") (pinfunction "GND_4") (pintype "bidirectional"))
      (node (ref "J13") (pin "5") (pinfunction "GND_5") (pintype "bidirectional"))
      (node (ref "J13") (pin "6") (pinfunction "GND_6") (pintype "bidirectional"))
      (node (ref "J13") (pin "7") (pinfunction "GND_7") (pintype "bidirectional"))
      (node (ref "J13") (pin "8") (pinfunction "GND_8") (pintype "bidirectional"))
      (node (ref "J14") (pin "3") (pinfunction "GND_3") (pintype "bidirectional"))
      (node (ref "J14") (pin "4") (pinfunction "GND_4") (pintype "bidirectional"))
      (node (ref "J14") (pin "5") (pinfunction "GND_5") (pintype "bidirectional"))
      (node (ref "J14") (pin "6") (pinfunction "GND_6") (pintype "bidirectional"))
      (node (ref "J14") (pin "7") (pinfunction "GND_7") (pintype "bidirectional"))
      (node (ref "J14") (pin "8") (pinfunction "GND_8") (pintype "bidirectional"))
      (node (ref "J15") (pin "3") (pinfunction "GND_3") (pintype "bidirectional"))
      (node (ref "J15") (pin "4") (pinfunction "GND_4") (pintype "bidirectional"))
      (node (ref "J15") (pin "5") (pinfunction "GND_5") (pintype "bidirectional"))
      (node (ref "J15") (pin "6") (pinfunction "GND_6") (pintype "bidirectional"))
      (node (ref "J15") (pin "7") (pinfunction "GND_7") (pintype "bidirectional"))
      (node (ref "J15") (pin "8") (pinfunction "GND_8") (pintype "bidirectional"))
      (node (ref "J16") (pin "3") (pinfunction "GND_3") (pintype "bidirectional"))
      (node (ref "J16") (pin "4") (pinfunction "GND_4") (pintype "bidirectional"))
      (node (ref "J16") (pin "5") (pinfunction "GND_5") (pintype "bidirectional"))
      (node (ref "J16") (pin "6") (pinfunction "GND_6") (pintype "bidirectional"))
      (node (ref "J16") (pin "7") (pinfunction "GND_7") (pintype "bidirectional"))
      (node (ref "J16") (pin "8") (pinfunction "GND_8") (pintype "bidirectional"))
      (node (ref "J17") (pin "3") (pinfunction "GND_3") (pintype "bidirectional"))
      (node (ref "J17") (pin "4") (pinfunction "GND_4") (pintype "bidirectional"))
      (node (ref "J17") (pin "5") (pinfunction "GND_5") (pintype "bidirectional"))
      (node (ref "J17") (pin "6") (pinfunction "GND_6") (pintype "bidirectional"))
      (node (ref "J17") (pin "7") (pinfunction "GND_7") (pintype "bidirectional"))
      (node (ref "J17") (pin "8") (pinfunction "GND_8") (pintype "bidirectional"))
      (node (ref "J18") (pin "3") (pinfunction "GND_3") (pintype "bidirectional"))
      (node (ref "J18") (pin "4") (pinfunction "GND_4") (pintype "bidirectional"))
      (node (ref "J18") (pin "5") (pinfunction "GND_5") (pintype "bidirectional"))
      (node (ref "J18") (pin "6") (pinfunction "GND_6") (pintype "bidirectional"))
      (node (ref "J18") (pin "7") (pinfunction "GND_7") (pintype "bidirectional"))
      (node (ref "J18") (pin "8") (pinfunction "GND_8") (pintype "bidirectional"))
      (node (ref "J19") (pin "3") (pinfunction "GND_3") (pintype "bidirectional"))
      (node (ref "J19") (pin "4") (pinfunction "GND_4") (pintype "bidirectional"))
      (node (ref "J19") (pin "5") (pinfunction "GND_5") (pintype "bidirectional"))
      (node (ref "J19") (pin "6") (pinfunction "GND_6") (pintype "bidirectional"))
      (node (ref "J19") (pin "7") (pinfunction "GND_7") (pintype "bidirectional"))
      (node (ref "J19") (pin "8") (pinfunction "GND_8") (pintype "bidirectional"))
      (node (ref "J2") (pin "3") (pinfunction "GND_3") (pintype "bidirectional"))
      (node (ref "J2") (pin "4") (pinfunction "GND_4") (pintype "bidirectional"))
      (node (ref "J2") (pin "5") (pinfunction "GND_5") (pintype "bidirectional"))
      (node (ref "J2") (pin "6") (pinfunction "GND_6") (pintype "bidirectional"))
      (node (ref "J2") (pin "7") (pinfunction "GND_7") (pintype "bidirectional"))
      (node (ref "J2") (pin "8") (pinfunction "GND_8") (pintype "bidirectional"))
      (node (ref "J20") (pin "3") (pinfunction "GND_3") (pintype "bidirectional"))
      (node (ref "J20") (pin "4") (pinfunction "GND_4") (pintype "bidirectional"))
      (node (ref "J20") (pin "5") (pinfunction "GND_5") (pintype "bidirectional"))
      (node (ref "J20") (pin "6") (pinfunction "GND_6") (pintype "bidirectional"))
      (node (ref "J20") (pin "7") (pinfunction "GND_7") (pintype "bidirectional"))
      (node (ref "J20") (pin "8") (pinfunction "GND_8") (pintype "bidirectional"))
      (node (ref "J21") (pin "3") (pinfunction "GND_3") (pintype "bidirectional"))
      (node (ref "J21") (pin "4") (pinfunction "GND_4") (pintype "bidirectional"))
      (node (ref "J21") (pin "5") (pinfunction "GND_5") (pintype "bidirectional"))
      (node (ref "J21") (pin "6") (pinfunction "GND_6") (pintype "bidirectional"))
      (node (ref "J21") (pin "7") (pinfunction "GND_7") (pintype "bidirectional"))
      (node (ref "J21") (pin "8") (pinfunction "GND_8") (pintype "bidirectional"))
      (node (ref "J22") (pin "3") (pinfunction "GND_3") (pintype "bidirectional"))
      (node (ref "J22") (pin "4") (pinfunction "GND_4") (pintype "bidirectional"))
      (node (ref "J22") (pin "5") (pinfunction "GND_5") (pintype "bidirectional"))
      (node (ref "J22") (pin "6") (pinfunction "GND_6") (pintype "bidirectional"))
      (node (ref "J22") (pin "7") (pinfunction "GND_7") (pintype "bidirectional"))
      (node (ref "J22") (pin "8") (pinfunction "GND_8") (pintype "bidirectional"))
      (node (ref "J23") (pin "3") (pinfunction "GND_3") (pintype "bidirectional"))
      (node (ref "J23") (pin "4") (pinfunction "GND_4") (pintype "bidirectional"))
      (node (ref "J23") (pin "5") (pinfunction "GND_5") (pintype "bidirectional"))
      (node (ref "J23") (pin "6") (pinfunction "GND_6") (pintype "bidirectional"))
      (node (ref "J23") (pin "7") (pinfunction "GND_7") (pintype "bidirectional"))
      (node (ref "J23") (pin "8") (pinfunction "GND_8") (pintype "bidirectional"))
      (node (ref "J24") (pin "3") (pinfunction "GND_3") (pintype "bidirectional"))
      (node (ref "J24") (pin "4") (pinfunction "GND_4") (pintype "bidirectional"))
      (node (ref "J24") (pin "5") (pinfunction "GND_5") (pintype "bidirectional"))
      (node (ref "J24") (pin "6") (pinfunction "GND_6") (pintype "bidirectional"))
      (node (ref "J24") (pin "7") (pinfunction "GND_7") (pintype "bidirectional"))
      (node (ref "J24") (pin "8") (pinfunction "GND_8") (pintype "bidirectional"))
      (node (ref "J25") (pin "3") (pinfunction "GND_3") (pintype "bidirectional"))
      (node (ref "J25") (pin "4") (pinfunction "GND_4") (pintype "bidirectional"))
      (node (ref "J25") (pin "5") (pinfunction "GND_5") (pintype "bidirectional"))
      (node (ref "J25") (pin "6") (pinfunction "GND_6") (pintype "bidirectional"))
      (node (ref "J25") (pin "7") (pinfunction "GND_7") (pintype "bidirectional"))
      (node (ref "J25") (pin "8") (pinfunction "GND_8") (pintype "bidirectional"))
      (node (ref "J26") (pin "3") (pinfunction "GND_3") (pintype "bidirectional"))
      (node (ref "J26") (pin "4") (pinfunction "GND_4") (pintype "bidirectional"))
      (node (ref "J26") (pin "5") (pinfunction "GND_5") (pintype "bidirectional"))
      (node (ref "J26") (pin "6") (pinfunction "GND_6") (pintype "bidirectional"))
      (node (ref "J26") (pin "7") (pinfunction "GND_7") (pintype "bidirectional"))
      (node (ref "J26") (pin "8") (pinfunction "GND_8") (pintype "bidirectional"))
      (node (ref "J3") (pin "3") (pinfunction "GND_3") (pintype "bidirectional"))
      (node (ref "J3") (pin "4") (pinfunction "GND_4") (pintype "bidirectional"))
      (node (ref "J3") (pin "5") (pinfunction "GND_5") (pintype "bidirectional"))
      (node (ref "J3") (pin "6") (pinfunction "GND_6") (pintype "bidirectional"))
      (node (ref "J3") (pin "7") (pinfunction "GND_7") (pintype "bidirectional"))
      (node (ref "J3") (pin "8") (pinfunction "GND_8") (pintype "bidirectional"))
      (node (ref "J4") (pin "3") (pinfunction "GND_3") (pintype "bidirectional"))
      (node (ref "J4") (pin "4") (pinfunction "GND_4") (pintype "bidirectional"))
      (node (ref "J4") (pin "5") (pinfunction "GND_5") (pintype "bidirectional"))
      (node (ref "J4") (pin "6") (pinfunction "GND_6") (pintype "bidirectional"))
      (node (ref "J4") (pin "7") (pinfunction "GND_7") (pintype "bidirectional"))
      (node (ref "J4") (pin "8") (pinfunction "GND_8") (pintype "bidirectional"))
      (node (ref "J5") (pin "3") (pinfunction "GND_3") (pintype "bidirectional"))
      (node (ref "J5") (pin "4") (pinfunction "GND_4") (pintype "bidirectional"))
      (node (ref "J5") (pin "5") (pinfunction "GND_5") (pintype "bidirectional"))
      (node (ref "J5") (pin "6") (pinfunction "GND_6") (pintype "bidirectional"))
      (node (ref "J5") (pin "7") (pinfunction "GND_7") (pintype "bidirectional"))
      (node (ref "J5") (pin "8") (pinfunction "GND_8") (pintype "bidirectional"))
      (node (ref "J6") (pin "3") (pinfunction "GND_3") (pintype "bidirectional"))
      (node (ref "J6") (pin "4") (pinfunction "GND_4") (pintype "bidirectional"))
      (node (ref "J6") (pin "5") (pinfunction "GND_5") (pintype "bidirectional"))
      (node (ref "J6") (pin "6") (pinfunction "GND_6") (pintype "bidirectional"))
      (node (ref "J6") (pin "7") (pinfunction "GND_7") (pintype "bidirectional"))
      (node (ref "J6") (pin "8") (pinfunction "GND_8") (pintype "bidirectional"))
      (node (ref "J7") (pin "3") (pinfunction "GND_3") (pintype "bidirectional"))
      (node (ref "J7") (pin "4") (pinfunction "GND_4") (pintype "bidirectional"))
      (node (ref "J7") (pin "5") (pinfunction "GND_5") (pintype "bidirectional"))
      (node (ref "J7") (pin "6") (pinfunction "GND_6") (pintype "bidirectional"))
      (node (ref "J7") (pin "7") (pinfunction "GND_7") (pintype "bidirectional"))
      (node (ref "J7") (pin "8") (pinfunction "GND_8") (pintype "bidirectional"))
      (node (ref "J8") (pin "3") (pinfunction "GND_3") (pintype "bidirectional"))
      (node (ref "J8") (pin "4") (pinfunction "GND_4") (pintype "bidirectional"))
      (node (ref "J8") (pin "5") (pinfunction "GND_5") (pintype "bidirectional"))
      (node (ref "J8") (pin "6") (pinfunction "GND_6") (pintype "bidirectional"))
      (node (ref "J8") (pin "7") (pinfunction "GND_7") (pintype "bidirectional"))
      (node (ref "J8") (pin "8") (pinfunction "GND_8") (pintype "bidirectional"))
      (node (ref "J9") (pin "3") (pinfunction "GND_3") (pintype "bidirectional"))
      (node (ref "J9") (pin "4") (pinfunction "GND_4") (pintype "bidirectional"))
      (node (ref "J9") (pin "5") (pinfunction "GND_5") (pintype "bidirectional"))
      (node (ref "J9") (pin "6") (pinfunction "GND_6") (pintype "bidirectional"))
      (node (ref "J9") (pin "7") (pinfunction "GND_7") (pintype "bidirectional"))
      (node (ref "J9") (pin "8") (pinfunction "GND_8") (pintype "bidirectional"))
      (node (ref "U$105") (pin "P$1") (pinfunction "VOLTAGE_P$1") (pintype "bidirectional"))
      (node (ref "U$105") (pin "P$2") (pinfunction "VOLTAGE_P$2") (pintype "bidirectional"))
      (node (ref "U$105") (pin "P$3") (pinfunction "VOLTAGE_P$3") (pintype "bidirectional"))
      (node (ref "U$31") (pin "GND@1") (pinfunction "GND_GND@1") (pintype "bidirectional"))
      (node (ref "U$31") (pin "GND@10") (pinfunction "GND_GND@10") (pintype "bidirectional"))
      (node (ref "U$31") (pin "GND@11") (pinfunction "GND_GND@11") (pintype "bidirectional"))
      (node (ref "U$31") (pin "GND@12") (pinfunction "GND_GND@12") (pintype "bidirectional"))
      (node (ref "U$31") (pin "GND@13") (pinfunction "GND_GND@13") (pintype "bidirectional"))
      (node (ref "U$31") (pin "GND@14") (pinfunction "GND_GND@14") (pintype "bidirectional"))
      (node (ref "U$31") (pin "GND@2") (pinfunction "GND_GND@2") (pintype "bidirectional"))
      (node (ref "U$31") (pin "GND@3") (pinfunction "GND_GND@3") (pintype "bidirectional"))
      (node (ref "U$31") (pin "GND@4") (pinfunction "GND_GND@4") (pintype "bidirectional"))
      (node (ref "U$31") (pin "GND@5") (pinfunction "GND_GND@5") (pintype "bidirectional"))
      (node (ref "U$31") (pin "GND@6") (pinfunction "GND_GND@6") (pintype "bidirectional"))
      (node (ref "U$31") (pin "GND@7") (pinfunction "GND_GND@7") (pintype "bidirectional"))
      (node (ref "U$31") (pin "GND@8") (pinfunction "GND_GND@8") (pintype "bidirectional"))
      (node (ref "U$31") (pin "GND@9") (pinfunction "GND_GND@9") (pintype "bidirectional"))
      (node (ref "U$6") (pin "P$1") (pinfunction "VOLTAGE_P$1") (pintype "bidirectional"))
      (node (ref "U$6") (pin "P$2") (pinfunction "VOLTAGE_P$2") (pintype "bidirectional"))
      (node (ref "U$6") (pin "P$3") (pinfunction "VOLTAGE_P$3") (pintype "bidirectional"))
      (node (ref "U$8") (pin "10") (pinfunction "GND_10") (pintype "bidirectional"))
      (node (ref "U$8") (pin "12") (pinfunction "GND_12") (pintype "bidirectional"))
      (node (ref "U$8") (pin "14") (pinfunction "GND_14") (pintype "bidirectional"))
      (node (ref "U$8") (pin "15") (pinfunction "GND_15") (pintype "bidirectional"))
      (node (ref "U$8") (pin "17") (pinfunction "GND_17") (pintype "bidirectional"))
      (node (ref "U$8") (pin "19") (pinfunction "GND_19") (pintype "bidirectional"))
      (node (ref "U$8") (pin "2") (pinfunction "GND_2") (pintype "bidirectional"))
      (node (ref "U$8") (pin "21") (pinfunction "GND_21") (pintype "bidirectional"))
      (node (ref "U$8") (pin "23") (pinfunction "GND_23") (pintype "bidirectional"))
      (node (ref "U$8") (pin "4") (pinfunction "GND_4") (pintype "bidirectional"))
      (node (ref "U$8") (pin "6") (pinfunction "GND_6") (pintype "bidirectional"))
      (node (ref "U$8") (pin "8") (pinfunction "GND_8") (pintype "bidirectional"))
    )
    (net (code "9") (name "Net-(U$8-AUDIO_IN)") (class "Default")
      (node (ref "U$2") (pin "P$1") (pinfunction "VOLTAGE_P$1") (pintype "bidirectional"))
      (node (ref "U$2") (pin "P$2") (pinfunction "VOLTAGE_P$2") (pintype "bidirectional"))
      (node (ref "U$2") (pin "P$3") (pinfunction "VOLTAGE_P$3") (pintype "bidirectional"))
      (node (ref "U$8") (pin "20") (pinfunction "AUDIO_IN_20") (pintype "bidirectional"))
    )
    (net (code "10") (name "Net-(U$8-AUDIO_OUT_LEFT)") (class "Default")
      (node (ref "U$29") (pin "P$1") (pinfunction "VOLTAGE_P$1") (pintype "bidirectional"))
      (node (ref "U$29") (pin "P$2") (pinfunction "VOLTAGE_P$2") (pintype "bidirectional"))
      (node (ref "U$29") (pin "P$3") (pinfunction "VOLTAGE_P$3") (pintype "bidirectional"))
      (node (ref "U$8") (pin "18") (pinfunction "AUDIO_OUT_LEFT_18") (pintype "bidirectional"))
    )
    (net (code "11") (name "Net-(U$8-AUDIO_OUT_RIGHT)") (class "Default")
      (node (ref "U$30") (pin "P$1") (pinfunction "VOLTAGE_P$1") (pintype "bidirectional"))
      (node (ref "U$30") (pin "P$2") (pinfunction "VOLTAGE_P$2") (pintype "bidirectional"))
      (node (ref "U$30") (pin "P$3") (pinfunction "VOLTAGE_P$3") (pintype "bidirectional"))
      (node (ref "U$8") (pin "16") (pinfunction "AUDIO_OUT_RIGHT_16") (pintype "bidirectional"))
    )
    (net (code "12") (name "Net-(U$8-MIDI)") (class "Default")
      (node (ref "U$1") (pin "P$1") (pinfunction "VOLTAGE_P$1") (pintype "bidirectional"))
      (node (ref "U$1") (pin "P$2") (pinfunction "VOLTAGE_P$2") (pintype "bidirectional"))
      (node (ref "U$1") (pin "P$3") (pinfunction "VOLTAGE_P$3") (pintype "bidirectional"))
      (node (ref "U$8") (pin "24") (pinfunction "MIDI_24") (pintype "bidirectional"))
    )
    (net (code "13") (name "VIN") (class "Default")
      (node (ref "U$104") (pin "P$1") (pinfunction "VOLTAGE_P$1") (pintype "bidirectional"))
      (node (ref "U$104") (pin "P$2") (pinfunction "VOLTAGE_P$2") (pintype "bidirectional"))
      (node (ref "U$104") (pin "P$3") (pinfunction "VOLTAGE_P$3") (pintype "bidirectional"))
      (node (ref "U$31") (pin "VIN@1") (pinfunction "VIN(18V)_VIN@1") (pintype "bidirectional"))
      (node (ref "U$31") (pin "VIN@2") (pinfunction "VIN(18V)_VIN@2") (pintype "bidirectional"))
      (node (ref "U$31") (pin "VIN@3") (pinfunction "VIN(18V)_VIN@3") (pintype "bidirectional"))
      (node (ref "U$31") (pin "VIN@4") (pinfunction "VIN(18V)_VIN@4") (pintype "bidirectional"))
      (node (ref "U$8") (pin "1") (pinfunction "VIN_1") (pintype "bidirectional"))
      (node (ref "U$8") (pin "3") (pinfunction "VIN_3") (pintype "bidirectional"))
      (node (ref "U$8") (pin "5") (pinfunction "VIN_5") (pintype "bidirectional"))
      (node (ref "U$8") (pin "7") (pinfunction "VIN_7") (pintype "bidirectional"))
      (node (ref "U$8") (pin "9") (pinfunction "VIN_9") (pintype "bidirectional"))
    )
  )
)
